# 1-Schematic_Computador_de_Mesa_Inteligen.net
KiCad netlist of a schematic drawn in EasyEDA
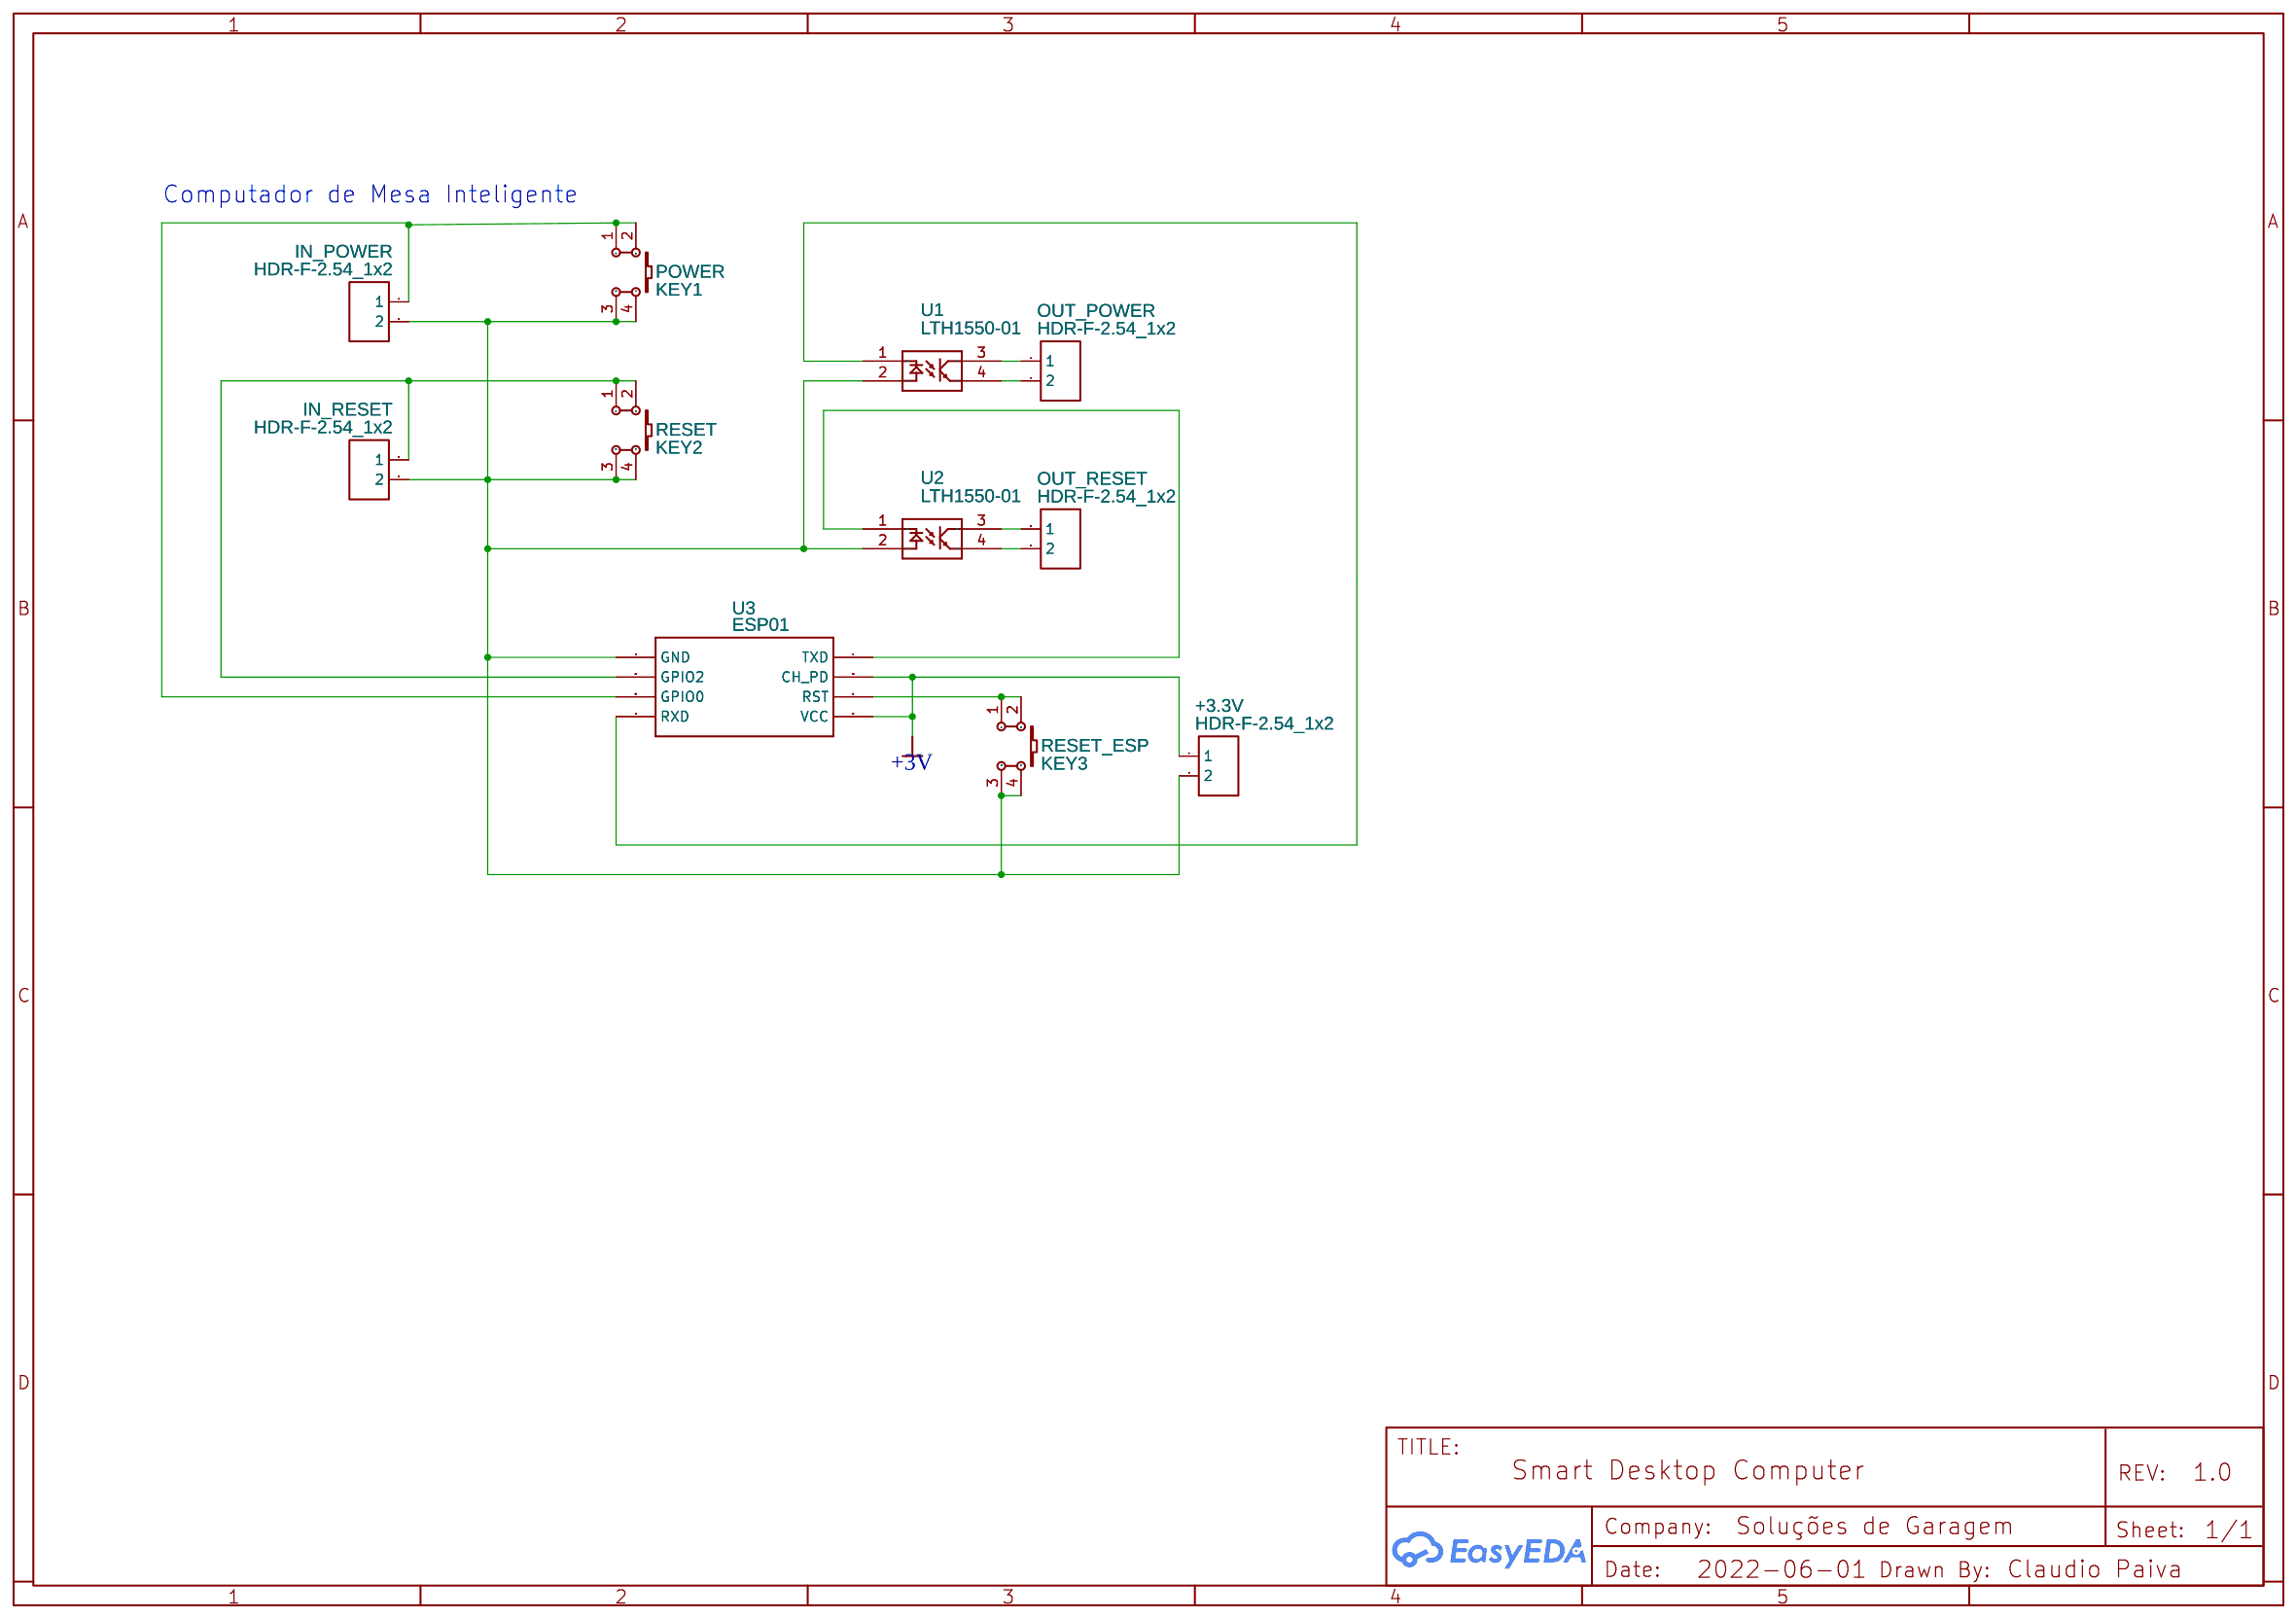
[diagram p0: schematic sheet]

(export (version "E")
  (design (tool "Eeschema 10.0.6"))
  (components
    (comp (ref "+3.3V")
      (value "HDR-F-2.54_1x2")
      (fields (field (name "BOM_Supplier Part") "C49661"))
      (libsource (lib "") (part "HDR-F-2.54_1x2"))
    )
    (comp (ref "IN_POWER")
      (value "HDR-F-2.54_1x2")
      (fields (field (name "BOM_Supplier Part") "C49661"))
      (libsource (lib "") (part "HDR-F-2.54_1x2_2"))
    )
    (comp (ref "IN_RESET")
      (value "HDR-F-2.54_1x2")
      (fields (field (name "BOM_Supplier Part") "C49661"))
      (libsource (lib "") (part "HDR-F-2.54_1x2_4"))
    )
    (comp (ref "OUT_POWER")
      (value "HDR-F-2.54_1x2")
      (fields (field (name "BOM_Supplier Part") "C49661"))
      (libsource (lib "") (part "HDR-F-2.54_1x2_3"))
    )
    (comp (ref "OUT_RESET")
      (value "HDR-F-2.54_1x2")
      (fields (field (name "BOM_Supplier Part") "C49661"))
      (libsource (lib "") (part "HDR-F-2.54_1x2_1"))
    )
    (comp (ref "POWER")
      (value "KEY1")
      (fields
        (field (name "BOM_Manufacturer Part") "K2-1102DP-E4SW-04")
        (field (name "BOM_Supplier Part") "C136684")
      )
      (libsource (lib "") (part "K4-6×6_TH_1"))
    )
    (comp (ref "RESET")
      (value "KEY2")
      (fields
        (field (name "BOM_Manufacturer Part") "K2-1102DP-E4SW-04")
        (field (name "BOM_Supplier Part") "C136684")
      )
      (libsource (lib "") (part "K4-6×6_TH_2"))
    )
    (comp (ref "RESET_ESP")
      (value "KEY3")
      (fields
        (field (name "BOM_Manufacturer Part") "K2-1102DP-E4SW-04")
        (field (name "BOM_Supplier Part") "C136684")
      )
      (libsource (lib "") (part "K4-6×6_TH"))
    )
    (comp (ref "U1") (value "LTH1550-01") (libsource (lib "") (part "LTH1550-01")))
    (comp (ref "U2") (value "LTH1550-01") (libsource (lib "") (part "LTH1550-01")))
    (comp (ref "U3") (value "ESP01") (libsource (lib "") (part "ESP01")))
  )
  (nets
    (net (code "1") (name "+3V") (class "Default")
      (node (ref "+3.3V") (pin "1") (pinfunction "1_1") (pintype "input"))
      (node (ref "U3") (pin "CH_PD") (pinfunction "CH_PD_CH_PD") (pintype "unspecified"))
      (node (ref "U3") (pin "VCC") (pinfunction "VCC_VCC") (pintype "unspecified"))
    )
    (net (code "2") (name "Net-(+3.3V-Pad2)") (class "Default")
      (node (ref "+3.3V") (pin "2") (pinfunction "2_2") (pintype "input"))
      (node (ref "IN_POWER") (pin "2") (pinfunction "2_2") (pintype "input"))
      (node (ref "IN_RESET") (pin "2") (pinfunction "2_2") (pintype "input"))
      (node (ref "POWER") (pin "3") (pinfunction "3_3") (pintype "unspecified"))
      (node (ref "POWER") (pin "4") (pinfunction "4_4") (pintype "unspecified"))
      (node (ref "RESET") (pin "3") (pinfunction "3_3") (pintype "unspecified"))
      (node (ref "RESET") (pin "4") (pinfunction "4_4") (pintype "unspecified"))
      (node (ref "RESET_ESP") (pin "3") (pinfunction "3_3") (pintype "unspecified"))
      (node (ref "RESET_ESP") (pin "4") (pinfunction "4_4") (pintype "unspecified"))
      (node (ref "U1") (pin "2") (pinfunction "2_2") (pintype "unspecified"))
      (node (ref "U2") (pin "2") (pinfunction "2_2") (pintype "unspecified"))
      (node (ref "U3") (pin "GND") (pinfunction "GND_GND") (pintype "unspecified"))
    )
    (net (code "3") (name "Net-(IN_POWER-Pad1)") (class "Default")
      (node (ref "IN_POWER") (pin "1") (pinfunction "1_1") (pintype "input"))
      (node (ref "POWER") (pin "1") (pinfunction "1_1") (pintype "unspecified"))
      (node (ref "POWER") (pin "2") (pinfunction "2_2") (pintype "unspecified"))
      (node (ref "U3") (pin "GPIO0") (pinfunction "GPIO0_GPIO0") (pintype "unspecified"))
    )
    (net (code "4") (name "Net-(IN_RESET-Pad1)") (class "Default")
      (node (ref "IN_RESET") (pin "1") (pinfunction "1_1") (pintype "input"))
      (node (ref "RESET") (pin "1") (pinfunction "1_1") (pintype "unspecified"))
      (node (ref "RESET") (pin "2") (pinfunction "2_2") (pintype "unspecified"))
      (node (ref "U3") (pin "GPIO2") (pinfunction "GPIO2_GPIO2") (pintype "unspecified"))
    )
    (net (code "5") (name "Net-(OUT_POWER-Pad1)") (class "Default")
      (node (ref "OUT_POWER") (pin "1") (pinfunction "1_1") (pintype "input"))
      (node (ref "U1") (pin "3") (pinfunction "3_3") (pintype "unspecified"))
    )
    (net (code "6") (name "Net-(OUT_POWER-Pad2)") (class "Default")
      (node (ref "OUT_POWER") (pin "2") (pinfunction "2_2") (pintype "input"))
      (node (ref "U1") (pin "4") (pinfunction "4_4") (pintype "unspecified"))
    )
    (net (code "7") (name "Net-(OUT_RESET-Pad1)") (class "Default")
      (node (ref "OUT_RESET") (pin "1") (pinfunction "1_1") (pintype "input"))
      (node (ref "U2") (pin "3") (pinfunction "3_3") (pintype "unspecified"))
    )
    (net (code "8") (name "Net-(OUT_RESET-Pad2)") (class "Default")
      (node (ref "OUT_RESET") (pin "2") (pinfunction "2_2") (pintype "input"))
      (node (ref "U2") (pin "4") (pinfunction "4_4") (pintype "unspecified"))
    )
    (net (code "9") (name "Net-(RESET_ESP-Pad1)") (class "Default")
      (node (ref "RESET_ESP") (pin "1") (pinfunction "1_1") (pintype "unspecified"))
      (node (ref "RESET_ESP") (pin "2") (pinfunction "2_2") (pintype "unspecified"))
      (node (ref "U3") (pin "RST") (pinfunction "RST_RST") (pintype "unspecified"))
    )
    (net (code "10") (name "Net-(U3-RXD)") (class "Default")
      (node (ref "U1") (pin "1") (pinfunction "1_1") (pintype "unspecified"))
      (node (ref "U3") (pin "RX") (pinfunction "RXD_RX") (pintype "unspecified"))
    )
    (net (code "11") (name "Net-(U3-TXD)") (class "Default")
      (node (ref "U2") (pin "1") (pinfunction "1_1") (pintype "unspecified"))
      (node (ref "U3") (pin "TX") (pinfunction "TXD_TX") (pintype "unspecified"))
    )
  )
)
